# Control.net
KiCad netlist of a schematic drawn in Altium Designer
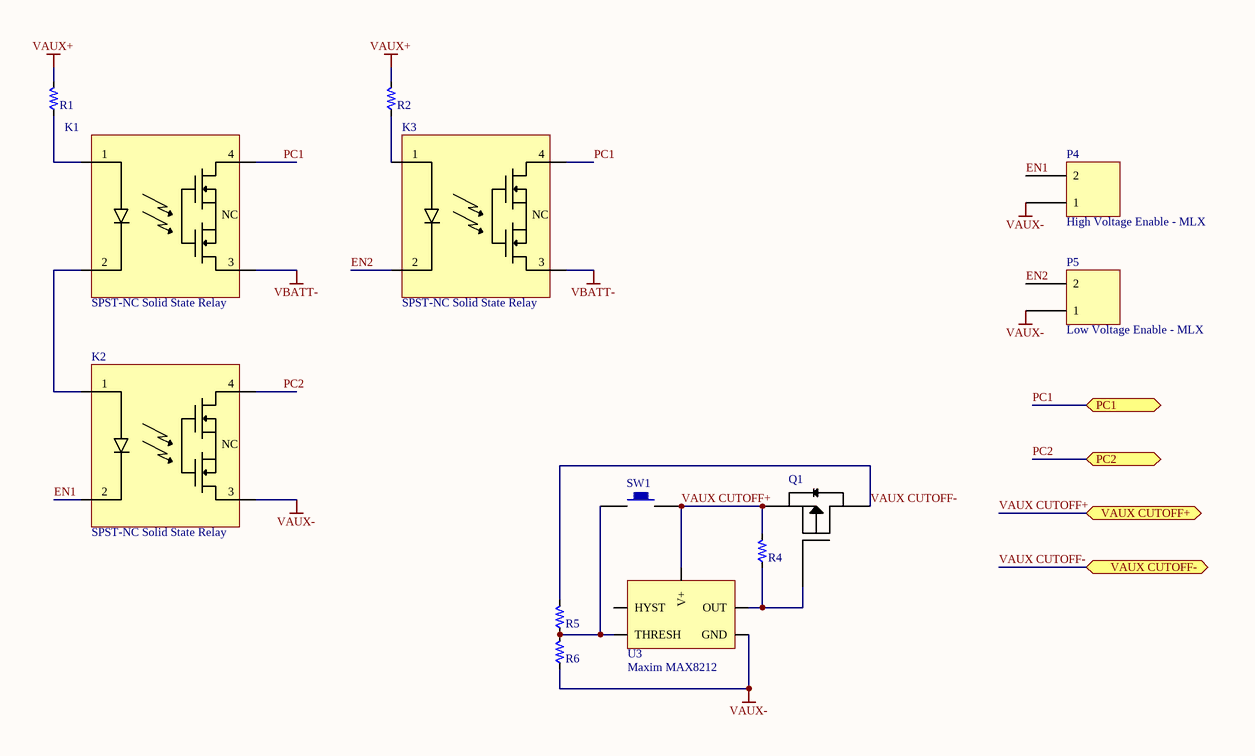
[diagram p0: Control.SchDoc]

(export (version "E")
  (design (tool "Eeschema 10.0.6"))
  (components
    (comp (ref "K1")
      (value "SPST-NC Solid State Relay")
      (footprint "SPST-NC Solid State Relay - IXYS")
      (libsource (lib "SPST-NC Solid State Relay") (part "SPST-NC Solid State Relay"))
    )
    (comp (ref "K2")
      (value "SPST-NC Solid State Relay")
      (footprint "SPST-NC Solid State Relay - IXYS")
      (libsource (lib "SPST-NC Solid State Relay") (part "SPST-NC Solid State Relay"))
    )
    (comp (ref "K3")
      (value "SPST-NC Solid State Relay")
      (footprint "SPST-NC Solid State Relay - IXYS")
      (libsource (lib "SPST-NC Solid State Relay") (part "SPST-NC Solid State Relay"))
    )
    (comp (ref "P4")
      (value "High Voltage Enable - MLX")
      (footprint "PCB_MLX_MICROFIT_1X2")
      (libsource (lib "Molex Microfit 3.0 1x2") (part "SCH_MLX_1X2"))
    )
    (comp (ref "P5")
      (value "Low Voltage Enable - MLX")
      (footprint "PCB_MLX_MICROFIT_1X2")
      (libsource (lib "Molex Microfit 3.0 1x2") (part "SCH_MLX_1X2"))
    )
    (comp (ref "Q1") (value "AOS DPAK  MOSFET") (libsource (lib "AOS DPAK PMOS") (part "AOS DPAK  MOSFET")))
    (comp (ref "R1")
      (value "SCH_GENERIC_RESISTOR_0603")
      (footprint "PCB_GENERIC_SMD_0603")
      (description "Generic SMD resistor 0603")
      (libsource (lib "Generic 0603 Resistor") (part "SCH_GENERIC_RESISTOR_0603"))
    )
    (comp (ref "R2")
      (value "SCH_GENERIC_RESISTOR_0603")
      (footprint "PCB_GENERIC_SMD_0603")
      (description "Generic SMD resistor 0603")
      (libsource (lib "Generic 0603 Resistor") (part "SCH_GENERIC_RESISTOR_0603"))
    )
    (comp (ref "R4")
      (value "SCH_GENERIC_RESISTOR_0603")
      (footprint "PCB_GENERIC_SMD_0603")
      (description "Generic SMD resistor 0603")
      (libsource (lib "Generic 0603 Resistor") (part "SCH_GENERIC_RESISTOR_0603"))
    )
    (comp (ref "R5")
      (value "SCH_GENERIC_RESISTOR_0603")
      (footprint "PCB_GENERIC_SMD_0603")
      (description "Generic SMD resistor 0603")
      (libsource (lib "Generic 0603 Resistor") (part "SCH_GENERIC_RESISTOR_0603"))
    )
    (comp (ref "R6")
      (value "SCH_GENERIC_RESISTOR_0603")
      (footprint "PCB_GENERIC_SMD_0603")
      (description "Generic SMD resistor 0603")
      (libsource (lib "Generic 0603 Resistor") (part "SCH_GENERIC_RESISTOR_0603"))
    )
    (comp (ref "SW1")
      (value "Push Button Switch")
      (footprint "Push Button Switch")
      (libsource (lib "Surface Mount Push Button Switch") (part "PushButtonSwitch"))
    )
    (comp (ref "U3") (value "Maxim MAX8212") (libsource (lib "Maxim MAX8212") (part "Maxim MAX8212")))
  )
  (nets
    (net (code "1") (name "/EN1") (class "Default")
      (node (ref "K2") (pin "2") (pinfunction "Control_-_2") (pintype "passive"))
      (node (ref "P4") (pin "2") (pinfunction "2_2") (pintype "passive"))
    )
    (net (code "2") (name "/EN2") (class "Default")
      (node (ref "K3") (pin "2") (pinfunction "Control_-_2") (pintype "passive"))
      (node (ref "P5") (pin "2") (pinfunction "2_2") (pintype "passive"))
    )
    (net (code "3") (name "/PC1") (class "Default")
      (node (ref "K1") (pin "4") (pinfunction "Load_4") (pintype "passive"))
      (node (ref "K3") (pin "4") (pinfunction "Load_4") (pintype "passive"))
    )
    (net (code "4") (name "/PC2") (class "Default")
      (node (ref "K2") (pin "4") (pinfunction "Load_4") (pintype "passive"))
    )
    (net (code "5") (name "/VAUX CUTOFF+") (class "Default")
      (node (ref "Q1") (pin "3") (pinfunction "S_3") (pintype "passive"))
      (node (ref "R4") (pin "2") (pinfunction "2_2") (pintype "passive"))
      (node (ref "SW1") (pin "2") (pinfunction "2_2") (pintype "passive"))
      (node (ref "U3") (pin "8") (pinfunction "V+_8") (pintype "passive"))
    )
    (net (code "6") (name "/VAUX CUTOFF-") (class "Default")
      (node (ref "Q1") (pin "4") (pinfunction "D_4") (pintype "passive"))
      (node (ref "R5") (pin "2") (pinfunction "2_2") (pintype "passive"))
    )
    (net (code "7") (name "Net-(K1-Control_+)") (class "Default")
      (node (ref "K1") (pin "1") (pinfunction "Control_+_1") (pintype "passive"))
      (node (ref "R1") (pin "1") (pinfunction "1_1") (pintype "passive"))
    )
    (net (code "8") (name "Net-(K1-Control_-)") (class "Default")
      (node (ref "K1") (pin "2") (pinfunction "Control_-_2") (pintype "passive"))
      (node (ref "K2") (pin "1") (pinfunction "Control_+_1") (pintype "passive"))
    )
    (net (code "9") (name "Net-(K3-Control_+)") (class "Default")
      (node (ref "K3") (pin "1") (pinfunction "Control_+_1") (pintype "passive"))
      (node (ref "R2") (pin "1") (pinfunction "1_1") (pintype "passive"))
    )
    (net (code "10") (name "Net-(Q1-G)") (class "Default")
      (node (ref "Q1") (pin "1") (pinfunction "G_1") (pintype "passive"))
      (node (ref "R4") (pin "1") (pinfunction "1_1") (pintype "passive"))
      (node (ref "U3") (pin "4") (pinfunction "OUT_4") (pintype "passive"))
    )
    (net (code "11") (name "Net-(U3-THRESH)") (class "Default")
      (node (ref "R5") (pin "1") (pinfunction "1_1") (pintype "passive"))
      (node (ref "R6") (pin "2") (pinfunction "2_2") (pintype "passive"))
      (node (ref "SW1") (pin "1") (pinfunction "1_1") (pintype "passive"))
      (node (ref "U3") (pin "3") (pinfunction "THRESH_3") (pintype "passive"))
    )
    (net (code "12") (name "VAUX+") (class "Default")
      (node (ref "R1") (pin "2") (pinfunction "2_2") (pintype "passive"))
      (node (ref "R2") (pin "2") (pinfunction "2_2") (pintype "passive"))
    )
    (net (code "13") (name "VAUX-") (class "Default")
      (node (ref "K2") (pin "3") (pinfunction "Load_3") (pintype "passive"))
      (node (ref "P4") (pin "1") (pinfunction "1_1") (pintype "passive"))
      (node (ref "P5") (pin "1") (pinfunction "1_1") (pintype "passive"))
      (node (ref "R6") (pin "1") (pinfunction "1_1") (pintype "passive"))
      (node (ref "U3") (pin "5") (pinfunction "GND_5") (pintype "passive"))
    )
    (net (code "14") (name "VBATT-") (class "Default")
      (node (ref "K1") (pin "3") (pinfunction "Load_3") (pintype "passive"))
      (node (ref "K3") (pin "3") (pinfunction "Load_3") (pintype "passive"))
    )
    (net (code "15") (name "unconnected-(U3-HYST-Pad2)") (class "Default")
      (node (ref "U3") (pin "2") (pinfunction "HYST_2") (pintype "passive"))
    )
  )
)
